# 2018_Dashboard.net
KiCad netlist of a schematic drawn in EAGLE
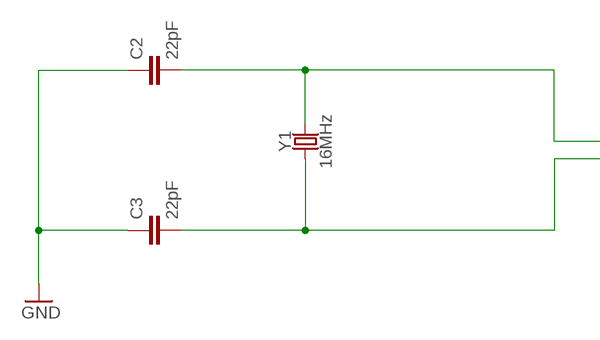
[diagram p0: schematic, sheet 1, part 1 of 2]
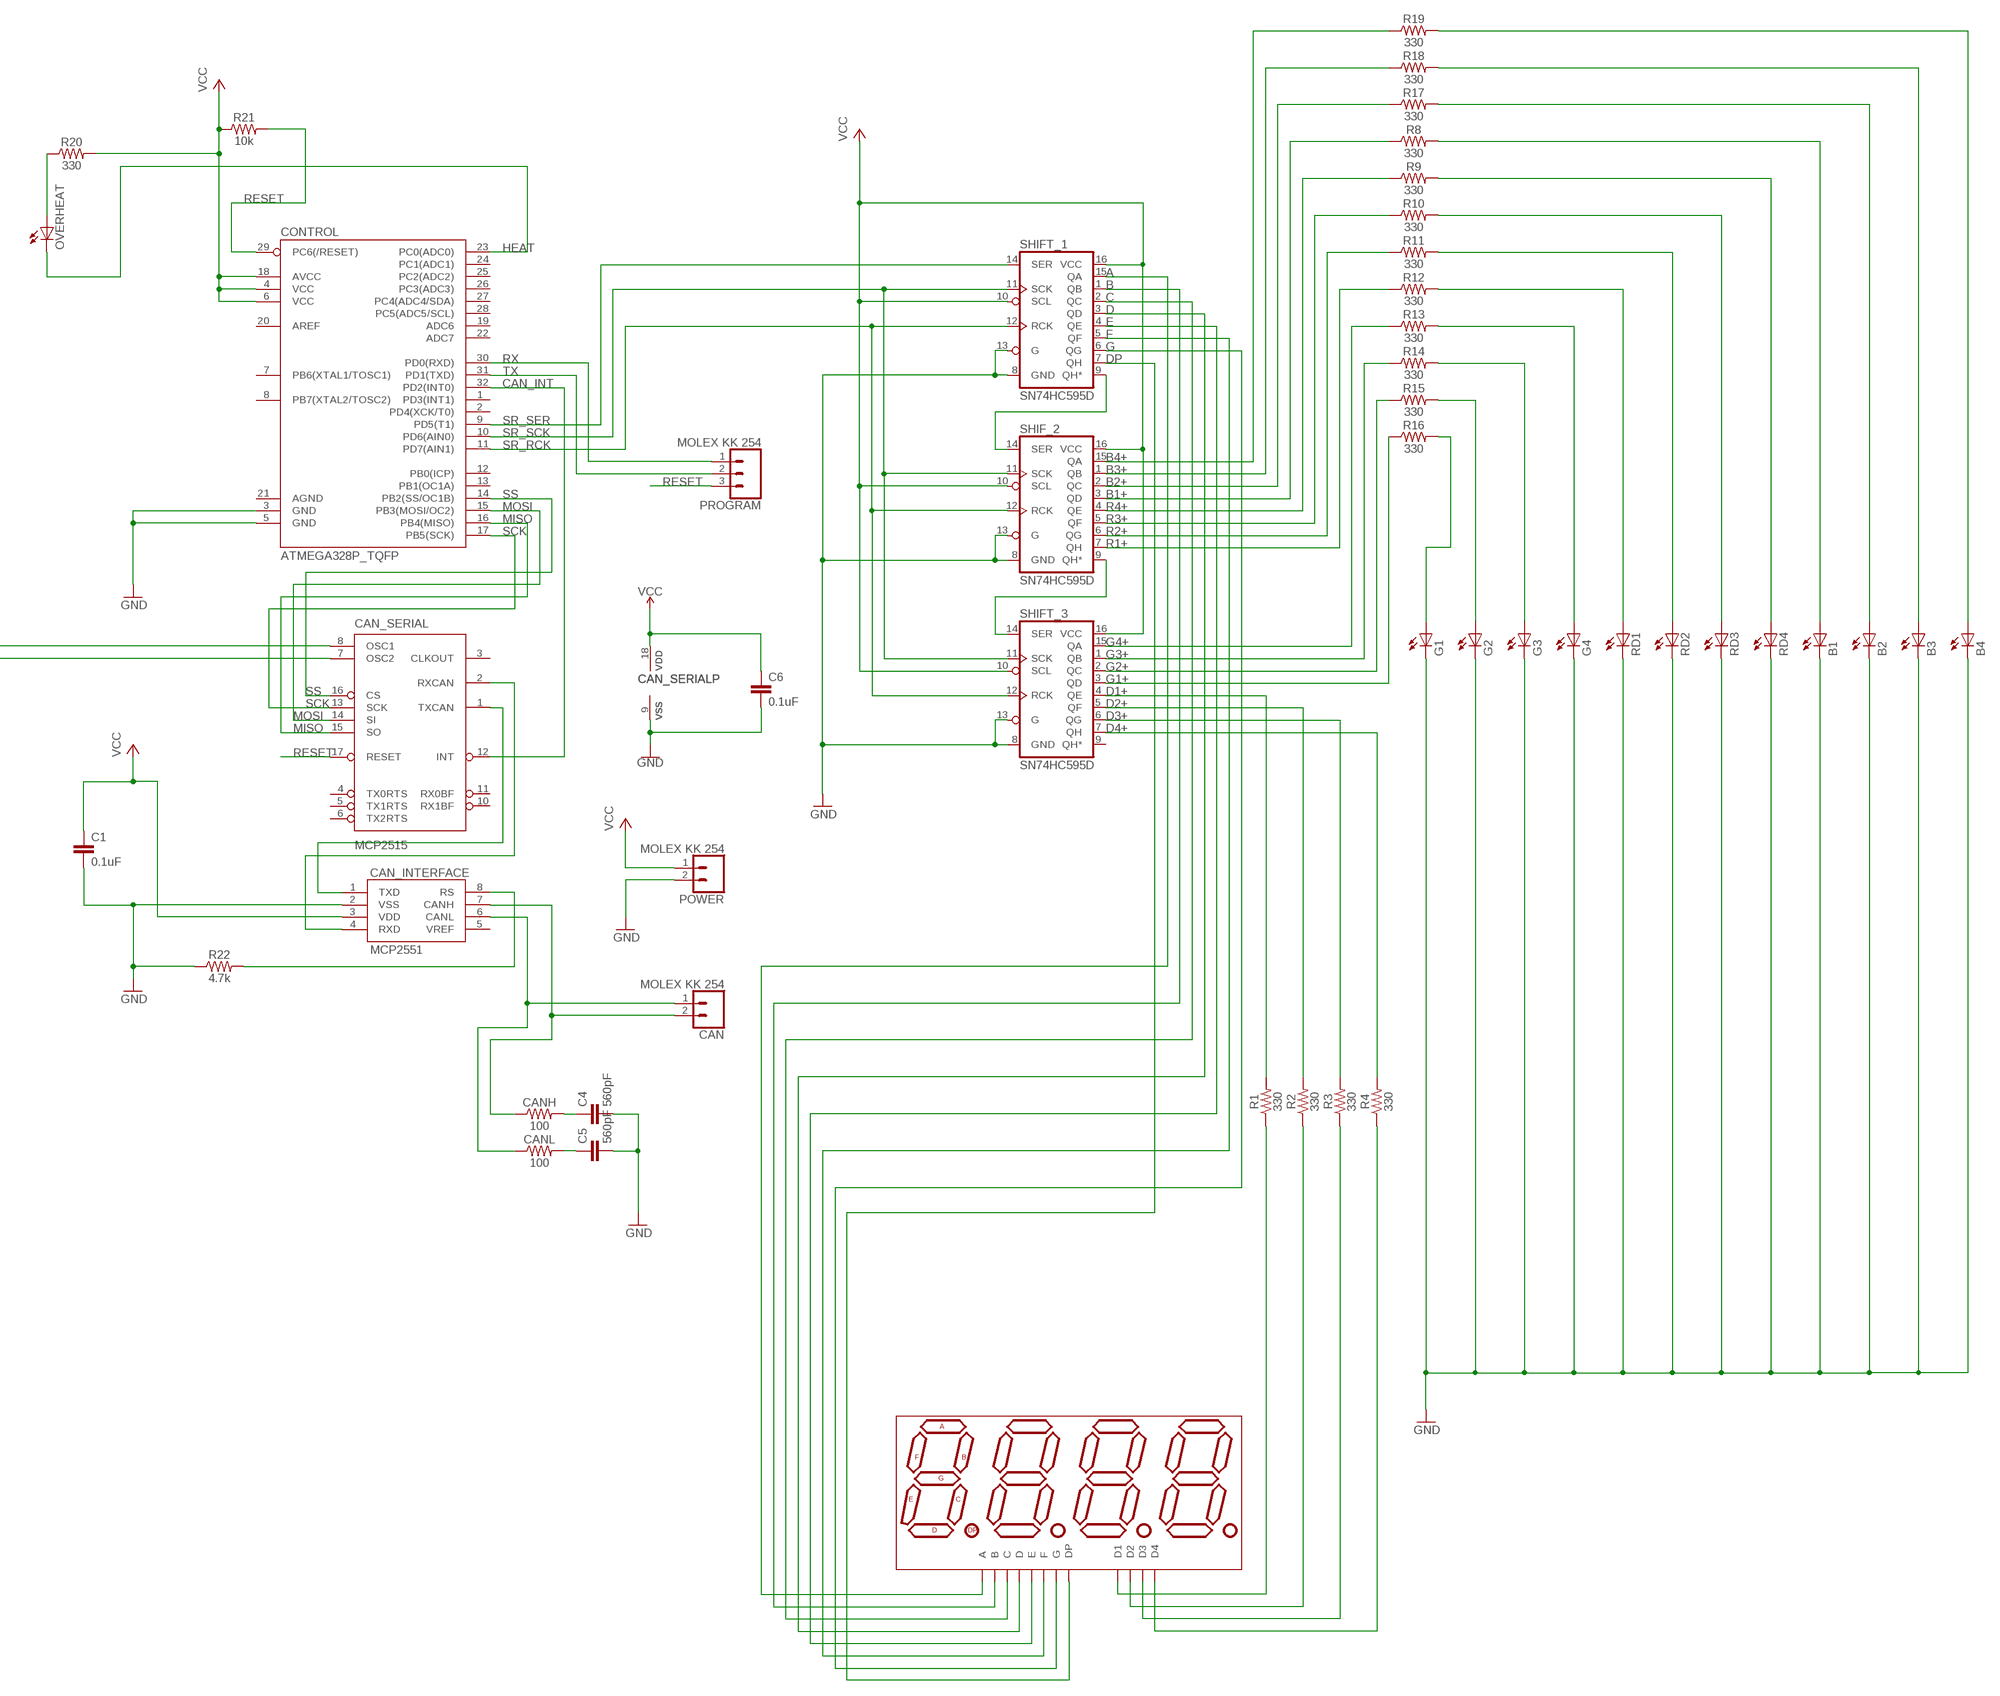
[diagram p1: schematic, sheet 1, part 2 of 2]

(export (version "E")
  (design (tool "Eeschema 10.0.6"))
  (components
    (comp (ref "B1")
      (value "TLLG4400")
      (footprint "eagle-import:LED3MM")
      (fields (field (name "MF") "VISHAY SEMICONDUCTOR"))
      (libsource (lib "eagle-import") (part "TLLG4400"))
    )
    (comp (ref "B2")
      (value "TLLG4400")
      (footprint "eagle-import:LED3MM")
      (fields (field (name "MF") "VISHAY SEMICONDUCTOR"))
      (libsource (lib "eagle-import") (part "TLLG4400"))
    )
    (comp (ref "B3")
      (value "TLLG4400")
      (footprint "eagle-import:LED3MM")
      (fields (field (name "MF") "VISHAY SEMICONDUCTOR"))
      (libsource (lib "eagle-import") (part "TLLG4400"))
    )
    (comp (ref "B4")
      (value "TLLG4400")
      (footprint "eagle-import:LED3MM")
      (fields (field (name "MF") "VISHAY SEMICONDUCTOR"))
      (libsource (lib "eagle-import") (part "TLLG4400"))
    )
    (comp (ref "C1")
      (value "0.1uF")
      (footprint "eagle-import:0603")
      (libsource (lib "eagle-import") (part "0.1UF-0603-25V-(+80/-20%)"))
    )
    (comp (ref "C2")
      (value "22pF")
      (footprint "eagle-import:0603")
      (libsource (lib "eagle-import") (part "22PF-0603-50V-5%"))
    )
    (comp (ref "C3")
      (value "22pF")
      (footprint "eagle-import:0603")
      (libsource (lib "eagle-import") (part "22PF-0603-50V-5%"))
    )
    (comp (ref "C4")
      (value "560pF")
      (footprint "eagle-import:0603")
      (libsource (lib "eagle-import") (part "560PF-0603-50V-5%"))
    )
    (comp (ref "C5")
      (value "560pF")
      (footprint "eagle-import:0603")
      (libsource (lib "eagle-import") (part "560PF-0603-50V-5%"))
    )
    (comp (ref "C6")
      (value "0.1uF")
      (footprint "eagle-import:0402")
      (libsource (lib "eagle-import") (part "0.1UF-0402-16V-10%"))
    )
    (comp (ref "CAN")
      (value "MOLEX KK 254")
      (footprint "eagle-import:1X02")
      (libsource (lib "eagle-import") (part "CONN_02"))
    )
    (comp (ref "CANH")
      (value "100")
      (footprint "eagle-import:0603")
      (libsource (lib "eagle-import") (part "100OHM-0603-1/4W-5%"))
    )
    (comp (ref "CANL")
      (value "100")
      (footprint "eagle-import:0603")
      (libsource (lib "eagle-import") (part "100OHM-0603-1/4W-5%"))
    )
    (comp (ref "CAN_INTERFACE")
      (value "MCP2551")
      (footprint "eagle-import:SO08")
      (libsource (lib "eagle-import") (part "MCP2551"))
    )
    (comp (ref "CAN_SERIAL")
      (value "MCP2515")
      (footprint "eagle-import:SO18W")
      (libsource (lib "eagle-import") (part "MCP2515(MCP2510)SO"))
    )
    (comp (ref "CONTROL")
      (value "ATMEGA328P_TQFP")
      (footprint "eagle-import:TQFP32-08")
      (libsource (lib "eagle-import") (part "ATMEGA328P_TQFP"))
    )
    (comp (ref "G1")
      (value "TLLG4400")
      (footprint "eagle-import:LED3MM")
      (fields (field (name "MF") "VISHAY SEMICONDUCTOR"))
      (libsource (lib "eagle-import") (part "TLLG4400"))
    )
    (comp (ref "G2")
      (value "TLLG4400")
      (footprint "eagle-import:LED3MM")
      (fields (field (name "MF") "VISHAY SEMICONDUCTOR"))
      (libsource (lib "eagle-import") (part "TLLG4400"))
    )
    (comp (ref "G3")
      (value "TLLG4400")
      (footprint "eagle-import:LED3MM")
      (fields (field (name "MF") "VISHAY SEMICONDUCTOR"))
      (libsource (lib "eagle-import") (part "TLLG4400"))
    )
    (comp (ref "G4")
      (value "TLLG4400")
      (footprint "eagle-import:LED3MM")
      (fields (field (name "MF") "VISHAY SEMICONDUCTOR"))
      (libsource (lib "eagle-import") (part "TLLG4400"))
    )
    (comp (ref "OVERHEAT")
      (value "TLLG4400")
      (footprint "eagle-import:LED3MM")
      (fields (field (name "MF") "VISHAY SEMICONDUCTOR"))
      (libsource (lib "eagle-import") (part "TLLG4400"))
    )
    (comp (ref "POWER")
      (value "MOLEX KK 254")
      (footprint "eagle-import:1X02")
      (libsource (lib "eagle-import") (part "CONN_02"))
    )
    (comp (ref "PROGRAM")
      (value "MOLEX KK 254")
      (footprint "eagle-import:1X03")
      (libsource (lib "eagle-import") (part "CONN_03"))
    )
    (comp (ref "R1")
      (value "330")
      (footprint "eagle-import:0603")
      (libsource (lib "eagle-import") (part "330OHM-0603-1/10W-1%"))
    )
    (comp (ref "R2")
      (value "330")
      (footprint "eagle-import:0603")
      (libsource (lib "eagle-import") (part "330OHM-0603-1/10W-1%"))
    )
    (comp (ref "R3")
      (value "330")
      (footprint "eagle-import:0603")
      (libsource (lib "eagle-import") (part "330OHM-0603-1/10W-1%"))
    )
    (comp (ref "R4")
      (value "330")
      (footprint "eagle-import:0603")
      (libsource (lib "eagle-import") (part "330OHM-0603-1/10W-1%"))
    )
    (comp (ref "R8")
      (value "330")
      (footprint "eagle-import:0603")
      (libsource (lib "eagle-import") (part "330OHM-0603-1/10W-1%"))
    )
    (comp (ref "R9")
      (value "330")
      (footprint "eagle-import:0603")
      (libsource (lib "eagle-import") (part "330OHM-0603-1/10W-1%"))
    )
    (comp (ref "R10")
      (value "330")
      (footprint "eagle-import:0603")
      (libsource (lib "eagle-import") (part "330OHM-0603-1/10W-1%"))
    )
    (comp (ref "R11")
      (value "330")
      (footprint "eagle-import:0603")
      (libsource (lib "eagle-import") (part "330OHM-0603-1/10W-1%"))
    )
    (comp (ref "R12")
      (value "330")
      (footprint "eagle-import:0603")
      (libsource (lib "eagle-import") (part "330OHM-0603-1/10W-1%"))
    )
    (comp (ref "R13")
      (value "330")
      (footprint "eagle-import:0603")
      (libsource (lib "eagle-import") (part "330OHM-0603-1/10W-1%"))
    )
    (comp (ref "R14")
      (value "330")
      (footprint "eagle-import:0603")
      (libsource (lib "eagle-import") (part "330OHM-0603-1/10W-1%"))
    )
    (comp (ref "R15")
      (value "330")
      (footprint "eagle-import:0603")
      (libsource (lib "eagle-import") (part "330OHM-0603-1/10W-1%"))
    )
    (comp (ref "R16")
      (value "330")
      (footprint "eagle-import:0603")
      (libsource (lib "eagle-import") (part "330OHM-0603-1/10W-1%"))
    )
    (comp (ref "R17")
      (value "330")
      (footprint "eagle-import:0603")
      (libsource (lib "eagle-import") (part "330OHM-0603-1/10W-1%"))
    )
    (comp (ref "R18")
      (value "330")
      (footprint "eagle-import:0603")
      (libsource (lib "eagle-import") (part "330OHM-0603-1/10W-1%"))
    )
    (comp (ref "R19")
      (value "330")
      (footprint "eagle-import:0603")
      (libsource (lib "eagle-import") (part "330OHM-0603-1/10W-1%"))
    )
    (comp (ref "R20")
      (value "330")
      (footprint "eagle-import:0603")
      (libsource (lib "eagle-import") (part "330OHM-0603-1/10W-1%"))
    )
    (comp (ref "R21")
      (value "10k")
      (footprint "eagle-import:0603")
      (libsource (lib "eagle-import") (part "10KOHM-0603-1/10W-1%"))
    )
    (comp (ref "R22")
      (value "4.7k")
      (footprint "eagle-import:0603")
      (libsource (lib "eagle-import") (part "4.7KOHM-0603-1/10W-1%"))
    )
    (comp (ref "RD1")
      (value "TLLG4400")
      (footprint "eagle-import:LED3MM")
      (fields (field (name "MF") "VISHAY SEMICONDUCTOR"))
      (libsource (lib "eagle-import") (part "TLLG4400"))
    )
    (comp (ref "RD2")
      (value "TLLG4400")
      (footprint "eagle-import:LED3MM")
      (fields (field (name "MF") "VISHAY SEMICONDUCTOR"))
      (libsource (lib "eagle-import") (part "TLLG4400"))
    )
    (comp (ref "RD3")
      (value "TLLG4400")
      (footprint "eagle-import:LED3MM")
      (fields (field (name "MF") "VISHAY SEMICONDUCTOR"))
      (libsource (lib "eagle-import") (part "TLLG4400"))
    )
    (comp (ref "RD4")
      (value "TLLG4400")
      (footprint "eagle-import:LED3MM")
      (fields (field (name "MF") "VISHAY SEMICONDUCTOR"))
      (libsource (lib "eagle-import") (part "TLLG4400"))
    )
    (comp (ref "SEVEN_SEGMENT")
      (value "ATA8041AB")
      (footprint "eagle-import:7-SEGMENT-4DIGIT-20MM")
      (libsource (lib "eagle-import") (part "7-SEGMENT-4DIGIT-20MM-BLUE"))
    )
    (comp (ref "SHIFT_1")
      (value "SN74HC595D")
      (footprint "eagle-import:SO16")
      (libsource (lib "eagle-import") (part "74595DHC"))
    )
    (comp (ref "SHIFT_3")
      (value "SN74HC595D")
      (footprint "eagle-import:SO16")
      (libsource (lib "eagle-import") (part "74595DHC"))
    )
    (comp (ref "SHIF_2")
      (value "SN74HC595D")
      (footprint "eagle-import:SO16")
      (libsource (lib "eagle-import") (part "74595DHC"))
    )
    (comp (ref "Y1")
      (value "16MHz")
      (footprint "eagle-import:HC49US")
      (libsource (lib "eagle-import") (part "CRYSTAL-16MHZPTH-HC49US"))
    )
  )
  (nets
    (net (code "1") (name "/A") (class "Default")
      (node (ref "SEVEN_SEGMENT") (pin "11") (pinfunction "A_11") (pintype "bidirectional"))
      (node (ref "SHIFT_1") (pin "15") (pinfunction "QA_15") (pintype "tri_state"))
    )
    (net (code "2") (name "/B") (class "Default")
      (node (ref "SEVEN_SEGMENT") (pin "7") (pinfunction "B_7") (pintype "bidirectional"))
      (node (ref "SHIFT_1") (pin "1") (pinfunction "QB_1") (pintype "tri_state"))
    )
    (net (code "3") (name "/B1+") (class "Default")
      (node (ref "R8") (pin "1") (pinfunction "1_1") (pintype "passive"))
      (node (ref "SHIF_2") (pin "3") (pinfunction "QD_3") (pintype "tri_state"))
    )
    (net (code "4") (name "/B2+") (class "Default")
      (node (ref "R17") (pin "1") (pinfunction "1_1") (pintype "passive"))
      (node (ref "SHIF_2") (pin "2") (pinfunction "QC_2") (pintype "tri_state"))
    )
    (net (code "5") (name "/B3+") (class "Default")
      (node (ref "R18") (pin "1") (pinfunction "1_1") (pintype "passive"))
      (node (ref "SHIF_2") (pin "1") (pinfunction "QB_1") (pintype "tri_state"))
    )
    (net (code "6") (name "/B4+") (class "Default")
      (node (ref "R19") (pin "1") (pinfunction "1_1") (pintype "passive"))
      (node (ref "SHIF_2") (pin "15") (pinfunction "QA_15") (pintype "tri_state"))
    )
    (net (code "7") (name "/C") (class "Default")
      (node (ref "SEVEN_SEGMENT") (pin "4") (pinfunction "C_4") (pintype "bidirectional"))
      (node (ref "SHIFT_1") (pin "2") (pinfunction "QC_2") (pintype "tri_state"))
    )
    (net (code "8") (name "/CAN_INT") (class "Default")
      (node (ref "CAN_SERIAL") (pin "12") (pinfunction "INT_12") (pintype "output"))
      (node (ref "CONTROL") (pin "32") (pinfunction "PD2(INT0)_32") (pintype "bidirectional"))
    )
    (net (code "9") (name "/D") (class "Default")
      (node (ref "SEVEN_SEGMENT") (pin "2") (pinfunction "D_2") (pintype "bidirectional"))
      (node (ref "SHIFT_1") (pin "3") (pinfunction "QD_3") (pintype "tri_state"))
    )
    (net (code "10") (name "/D1+") (class "Default")
      (node (ref "R1") (pin "2") (pinfunction "2_2") (pintype "passive"))
      (node (ref "SHIFT_3") (pin "4") (pinfunction "QE_4") (pintype "tri_state"))
    )
    (net (code "11") (name "/D2+") (class "Default")
      (node (ref "R2") (pin "2") (pinfunction "2_2") (pintype "passive"))
      (node (ref "SHIFT_3") (pin "5") (pinfunction "QF_5") (pintype "tri_state"))
    )
    (net (code "12") (name "/D3+") (class "Default")
      (node (ref "R3") (pin "2") (pinfunction "2_2") (pintype "passive"))
      (node (ref "SHIFT_3") (pin "6") (pinfunction "QG_6") (pintype "tri_state"))
    )
    (net (code "13") (name "/D4+") (class "Default")
      (node (ref "R4") (pin "2") (pinfunction "2_2") (pintype "passive"))
      (node (ref "SHIFT_3") (pin "7") (pinfunction "QH_7") (pintype "tri_state"))
    )
    (net (code "14") (name "/DP") (class "Default")
      (node (ref "SEVEN_SEGMENT") (pin "3") (pinfunction "DP_3") (pintype "bidirectional"))
      (node (ref "SHIFT_1") (pin "7") (pinfunction "QH_7") (pintype "tri_state"))
    )
    (net (code "15") (name "/E") (class "Default")
      (node (ref "SEVEN_SEGMENT") (pin "1") (pinfunction "E_1") (pintype "bidirectional"))
      (node (ref "SHIFT_1") (pin "4") (pinfunction "QE_4") (pintype "tri_state"))
    )
    (net (code "16") (name "/F") (class "Default")
      (node (ref "SEVEN_SEGMENT") (pin "10") (pinfunction "F_10") (pintype "bidirectional"))
      (node (ref "SHIFT_1") (pin "5") (pinfunction "QF_5") (pintype "tri_state"))
    )
    (net (code "17") (name "/G") (class "Default")
      (node (ref "SEVEN_SEGMENT") (pin "5") (pinfunction "G_5") (pintype "bidirectional"))
      (node (ref "SHIFT_1") (pin "6") (pinfunction "QG_6") (pintype "tri_state"))
    )
    (net (code "18") (name "/G1+") (class "Default")
      (node (ref "R16") (pin "1") (pinfunction "1_1") (pintype "passive"))
      (node (ref "SHIFT_3") (pin "3") (pinfunction "QD_3") (pintype "tri_state"))
    )
    (net (code "19") (name "/G2+") (class "Default")
      (node (ref "R15") (pin "1") (pinfunction "1_1") (pintype "passive"))
      (node (ref "SHIFT_3") (pin "2") (pinfunction "QC_2") (pintype "tri_state"))
    )
    (net (code "20") (name "/G3+") (class "Default")
      (node (ref "R14") (pin "1") (pinfunction "1_1") (pintype "passive"))
      (node (ref "SHIFT_3") (pin "1") (pinfunction "QB_1") (pintype "tri_state"))
    )
    (net (code "21") (name "/G4+") (class "Default")
      (node (ref "R13") (pin "1") (pinfunction "1_1") (pintype "passive"))
      (node (ref "SHIFT_3") (pin "15") (pinfunction "QA_15") (pintype "tri_state"))
    )
    (net (code "22") (name "/HEAT") (class "Default")
      (node (ref "CONTROL") (pin "23") (pinfunction "PC0(ADC0)_23") (pintype "bidirectional"))
      (node (ref "OVERHEAT") (pin "K") (pinfunction "C_K") (pintype "passive"))
    )
    (net (code "23") (name "/MISO") (class "Default")
      (node (ref "CAN_SERIAL") (pin "15") (pinfunction "SO_15") (pintype "output"))
      (node (ref "CONTROL") (pin "16") (pinfunction "PB4(MISO)_16") (pintype "bidirectional"))
    )
    (net (code "24") (name "/MOSI") (class "Default")
      (node (ref "CAN_SERIAL") (pin "14") (pinfunction "SI_14") (pintype "input"))
      (node (ref "CONTROL") (pin "15") (pinfunction "PB3(MOSI/OC2)_15") (pintype "bidirectional"))
    )
    (net (code "25") (name "/R1+") (class "Default")
      (node (ref "R12") (pin "1") (pinfunction "1_1") (pintype "passive"))
      (node (ref "SHIF_2") (pin "7") (pinfunction "QH_7") (pintype "tri_state"))
    )
    (net (code "26") (name "/R2+") (class "Default")
      (node (ref "R11") (pin "1") (pinfunction "1_1") (pintype "passive"))
      (node (ref "SHIF_2") (pin "6") (pinfunction "QG_6") (pintype "tri_state"))
    )
    (net (code "27") (name "/R3+") (class "Default")
      (node (ref "R10") (pin "1") (pinfunction "1_1") (pintype "passive"))
      (node (ref "SHIF_2") (pin "5") (pinfunction "QF_5") (pintype "tri_state"))
    )
    (net (code "28") (name "/R4+") (class "Default")
      (node (ref "R9") (pin "1") (pinfunction "1_1") (pintype "passive"))
      (node (ref "SHIF_2") (pin "4") (pinfunction "QE_4") (pintype "tri_state"))
    )
    (net (code "29") (name "/RESET") (class "Default")
      (node (ref "CAN_SERIAL") (pin "17") (pinfunction "RESET_17") (pintype "input"))
      (node (ref "CONTROL") (pin "29") (pinfunction "PC6(/RESET)_29") (pintype "bidirectional"))
      (node (ref "PROGRAM") (pin "3") (pinfunction "3_3") (pintype "passive"))
      (node (ref "R21") (pin "2") (pinfunction "2_2") (pintype "passive"))
    )
    (net (code "30") (name "/RX") (class "Default")
      (node (ref "CONTROL") (pin "30") (pinfunction "PD0(RXD)_30") (pintype "bidirectional"))
      (node (ref "PROGRAM") (pin "1") (pinfunction "1_1") (pintype "passive"))
    )
    (net (code "31") (name "/SCK") (class "Default")
      (node (ref "CAN_SERIAL") (pin "13") (pinfunction "SCK_13") (pintype "input"))
      (node (ref "CONTROL") (pin "17") (pinfunction "PB5(SCK)_17") (pintype "bidirectional"))
    )
    (net (code "32") (name "/SR_RCK") (class "Default")
      (node (ref "CONTROL") (pin "11") (pinfunction "PD7(AIN1)_11") (pintype "bidirectional"))
      (node (ref "SHIFT_1") (pin "12") (pinfunction "RCK_12") (pintype "input"))
      (node (ref "SHIFT_3") (pin "12") (pinfunction "RCK_12") (pintype "input"))
      (node (ref "SHIF_2") (pin "12") (pinfunction "RCK_12") (pintype "input"))
    )
    (net (code "33") (name "/SR_SCK") (class "Default")
      (node (ref "CONTROL") (pin "10") (pinfunction "PD6(AIN0)_10") (pintype "bidirectional"))
      (node (ref "SHIFT_1") (pin "11") (pinfunction "SCK_11") (pintype "input"))
      (node (ref "SHIFT_3") (pin "11") (pinfunction "SCK_11") (pintype "input"))
      (node (ref "SHIF_2") (pin "11") (pinfunction "SCK_11") (pintype "input"))
    )
    (net (code "34") (name "/SR_SER") (class "Default")
      (node (ref "CONTROL") (pin "9") (pinfunction "PD5(T1)_9") (pintype "bidirectional"))
      (node (ref "SHIFT_1") (pin "14") (pinfunction "SER_14") (pintype "input"))
    )
    (net (code "35") (name "/SS") (class "Default")
      (node (ref "CAN_SERIAL") (pin "16") (pinfunction "CS_16") (pintype "input"))
      (node (ref "CONTROL") (pin "14") (pinfunction "PB2(SS/OC1B)_14") (pintype "bidirectional"))
    )
    (net (code "36") (name "/TX") (class "Default")
      (node (ref "CONTROL") (pin "31") (pinfunction "PD1(TXD)_31") (pintype "bidirectional"))
      (node (ref "PROGRAM") (pin "2") (pinfunction "2_2") (pintype "passive"))
    )
    (net (code "37") (name "GND") (class "Default")
      (node (ref "B1") (pin "K") (pinfunction "C_K") (pintype "passive"))
      (node (ref "B2") (pin "K") (pinfunction "C_K") (pintype "passive"))
      (node (ref "B3") (pin "K") (pinfunction "C_K") (pintype "passive"))
      (node (ref "B4") (pin "K") (pinfunction "C_K") (pintype "passive"))
      (node (ref "C1") (pin "2") (pinfunction "2_2") (pintype "passive"))
      (node (ref "C2") (pin "1") (pinfunction "1_1") (pintype "passive"))
      (node (ref "C3") (pin "1") (pinfunction "1_1") (pintype "passive"))
      (node (ref "C4") (pin "2") (pinfunction "2_2") (pintype "passive"))
      (node (ref "C5") (pin "2") (pinfunction "2_2") (pintype "passive"))
      (node (ref "C6") (pin "2") (pinfunction "2_2") (pintype "passive"))
      (node (ref "CAN_INTERFACE") (pin "2") (pinfunction "VSS_2") (pintype "bidirectional"))
      (node (ref "CAN_SERIAL") (pin "9") (pinfunction "VSS_9") (pintype "power_in"))
      (node (ref "CONTROL") (pin "3") (pinfunction "GND_3") (pintype "bidirectional"))
      (node (ref "CONTROL") (pin "5") (pinfunction "GND_5") (pintype "bidirectional"))
      (node (ref "G1") (pin "K") (pinfunction "C_K") (pintype "passive"))
      (node (ref "G2") (pin "K") (pinfunction "C_K") (pintype "passive"))
      (node (ref "G3") (pin "K") (pinfunction "C_K") (pintype "passive"))
      (node (ref "G4") (pin "K") (pinfunction "C_K") (pintype "passive"))
      (node (ref "POWER") (pin "2") (pinfunction "2_2") (pintype "passive"))
      (node (ref "R22") (pin "1") (pinfunction "1_1") (pintype "passive"))
      (node (ref "RD1") (pin "K") (pinfunction "C_K") (pintype "passive"))
      (node (ref "RD2") (pin "K") (pinfunction "C_K") (pintype "passive"))
      (node (ref "RD3") (pin "K") (pinfunction "C_K") (pintype "passive"))
      (node (ref "RD4") (pin "K") (pinfunction "C_K") (pintype "passive"))
      (node (ref "SHIFT_1") (pin "13") (pinfunction "G_13") (pintype "input"))
      (node (ref "SHIFT_1") (pin "8") (pinfunction "GND_8") (pintype "power_in"))
      (node (ref "SHIFT_3") (pin "13") (pinfunction "G_13") (pintype "input"))
      (node (ref "SHIFT_3") (pin "8") (pinfunction "GND_8") (pintype "power_in"))
      (node (ref "SHIF_2") (pin "13") (pinfunction "G_13") (pintype "input"))
      (node (ref "SHIF_2") (pin "8") (pinfunction "GND_8") (pintype "power_in"))
    )
    (net (code "38") (name "Net-(B1-PadA)") (class "Default")
      (node (ref "B1") (pin "A") (pinfunction "A_A") (pintype "passive"))
      (node (ref "R8") (pin "2") (pinfunction "2_2") (pintype "passive"))
    )
    (net (code "39") (name "Net-(B2-PadA)") (class "Default")
      (node (ref "B2") (pin "A") (pinfunction "A_A") (pintype "passive"))
      (node (ref "R17") (pin "2") (pinfunction "2_2") (pintype "passive"))
    )
    (net (code "40") (name "Net-(B3-PadA)") (class "Default")
      (node (ref "B3") (pin "A") (pinfunction "A_A") (pintype "passive"))
      (node (ref "R18") (pin "2") (pinfunction "2_2") (pintype "passive"))
    )
    (net (code "41") (name "Net-(B4-PadA)") (class "Default")
      (node (ref "B4") (pin "A") (pinfunction "A_A") (pintype "passive"))
      (node (ref "R19") (pin "2") (pinfunction "2_2") (pintype "passive"))
    )
    (net (code "42") (name "Net-(C4-Pad1)") (class "Default")
      (node (ref "C4") (pin "1") (pinfunction "1_1") (pintype "passive"))
      (node (ref "CANH") (pin "2") (pinfunction "2_2") (pintype "passive"))
    )
    (net (code "43") (name "Net-(C5-Pad1)") (class "Default")
      (node (ref "C5") (pin "1") (pinfunction "1_1") (pintype "passive"))
      (node (ref "CANL") (pin "2") (pinfunction "2_2") (pintype "passive"))
    )
    (net (code "44") (name "Net-(CAN_INTERFACE-CANH)") (class "Default")
      (node (ref "CAN") (pin "2") (pinfunction "2_2") (pintype "passive"))
      (node (ref "CANH") (pin "1") (pinfunction "1_1") (pintype "passive"))
      (node (ref "CAN_INTERFACE") (pin "7") (pinfunction "CANH_7") (pintype "bidirectional"))
    )
    (net (code "45") (name "Net-(CAN_INTERFACE-CANL)") (class "Default")
      (node (ref "CAN") (pin "1") (pinfunction "1_1") (pintype "passive"))
      (node (ref "CANL") (pin "1") (pinfunction "1_1") (pintype "passive"))
      (node (ref "CAN_INTERFACE") (pin "6") (pinfunction "CANL_6") (pintype "bidirectional"))
    )
    (net (code "46") (name "Net-(CAN_INTERFACE-RS)") (class "Default")
      (node (ref "CAN_INTERFACE") (pin "8") (pinfunction "RS_8") (pintype "bidirectional"))
      (node (ref "R22") (pin "2") (pinfunction "2_2") (pintype "passive"))
    )
    (net (code "47") (name "Net-(CAN_INTERFACE-RXD)") (class "Default")
      (node (ref "CAN_INTERFACE") (pin "4") (pinfunction "RXD_4") (pintype "bidirectional"))
      (node (ref "CAN_SERIAL") (pin "2") (pinfunction "RXCAN_2") (pintype "input"))
    )
    (net (code "48") (name "Net-(CAN_INTERFACE-TXD)") (class "Default")
      (node (ref "CAN_INTERFACE") (pin "1") (pinfunction "TXD_1") (pintype "bidirectional"))
      (node (ref "CAN_SERIAL") (pin "1") (pinfunction "TXCAN_1") (pintype "output"))
    )
    (net (code "49") (name "Net-(CAN_SERIALA-OSC1)") (class "Default")
      (node (ref "C2") (pin "2") (pinfunction "2_2") (pintype "passive"))
      (node (ref "CAN_SERIAL") (pin "8") (pinfunction "OSC1_8") (pintype "input"))
      (node (ref "Y1") (pin "2") (pinfunction "2_2") (pintype "passive"))
    )
    (net (code "50") (name "Net-(CAN_SERIALA-OSC2)") (class "Default")
      (node (ref "C3") (pin "2") (pinfunction "2_2") (pintype "passive"))
      (node (ref "CAN_SERIAL") (pin "7") (pinfunction "OSC2_7") (pintype "output"))
      (node (ref "Y1") (pin "1") (pinfunction "1_1") (pintype "passive"))
    )
    (net (code "51") (name "Net-(G1-PadA)") (class "Default")
      (node (ref "G1") (pin "A") (pinfunction "A_A") (pintype "passive"))
      (node (ref "R16") (pin "2") (pinfunction "2_2") (pintype "passive"))
    )
    (net (code "52") (name "Net-(G2-PadA)") (class "Default")
      (node (ref "G2") (pin "A") (pinfunction "A_A") (pintype "passive"))
      (node (ref "R15") (pin "2") (pinfunction "2_2") (pintype "passive"))
    )
    (net (code "53") (name "Net-(G3-PadA)") (class "Default")
      (node (ref "G3") (pin "A") (pinfunction "A_A") (pintype "passive"))
      (node (ref "R14") (pin "2") (pinfunction "2_2") (pintype "passive"))
    )
    (net (code "54") (name "Net-(G4-PadA)") (class "Default")
      (node (ref "G4") (pin "A") (pinfunction "A_A") (pintype "passive"))
      (node (ref "R13") (pin "2") (pinfunction "2_2") (pintype "passive"))
    )
    (net (code "55") (name "Net-(OVERHEAT-PadA)") (class "Default")
      (node (ref "OVERHEAT") (pin "A") (pinfunction "A_A") (pintype "passive"))
      (node (ref "R20") (pin "1") (pinfunction "1_1") (pintype "passive"))
    )
    (net (code "56") (name "Net-(R9-Pad2)") (class "Default")
      (node (ref "R9") (pin "2") (pinfunction "2_2") (pintype "passive"))
      (node (ref "RD4") (pin "A") (pinfunction "A_A") (pintype "passive"))
    )
    (net (code "57") (name "Net-(R10-Pad2)") (class "Default")
      (node (ref "R10") (pin "2") (pinfunction "2_2") (pintype "passive"))
      (node (ref "RD3") (pin "A") (pinfunction "A_A") (pintype "passive"))
    )
    (net (code "58") (name "Net-(R11-Pad2)") (class "Default")
      (node (ref "R11") (pin "2") (pinfunction "2_2") (pintype "passive"))
      (node (ref "RD2") (pin "A") (pinfunction "A_A") (pintype "passive"))
    )
    (net (code "59") (name "Net-(R12-Pad2)") (class "Default")
      (node (ref "R12") (pin "2") (pinfunction "2_2") (pintype "passive"))
      (node (ref "RD1") (pin "A") (pinfunction "A_A") (pintype "passive"))
    )
    (net (code "60") (name "Net-(SEVEN_SEGMENT-D1)") (class "Default")
      (node (ref "R1") (pin "1") (pinfunction "1_1") (pintype "passive"))
      (node (ref "SEVEN_SEGMENT") (pin "12") (pinfunction "D1_12") (pintype "bidirectional"))
    )
    (net (code "61") (name "Net-(SEVEN_SEGMENT-D2)") (class "Default")
      (node (ref "R2") (pin "1") (pinfunction "1_1") (pintype "passive"))
      (node (ref "SEVEN_SEGMENT") (pin "9") (pinfunction "D2_9") (pintype "bidirectional"))
    )
    (net (code "62") (name "Net-(SEVEN_SEGMENT-D3)") (class "Default")
      (node (ref "R3") (pin "1") (pinfunction "1_1") (pintype "passive"))
      (node (ref "SEVEN_SEGMENT") (pin "8") (pinfunction "D3_8") (pintype "bidirectional"))
    )
    (net (code "63") (name "Net-(SEVEN_SEGMENT-D4)") (class "Default")
      (node (ref "R4") (pin "1") (pinfunction "1_1") (pintype "passive"))
      (node (ref "SEVEN_SEGMENT") (pin "6") (pinfunction "D4_6") (pintype "bidirectional"))
    )
    (net (code "64") (name "Net-(SHIFT_1-QH*)") (class "Default")
      (node (ref "SHIFT_1") (pin "9") (pinfunction "QH*_9") (pintype "tri_state"))
      (node (ref "SHIF_2") (pin "14") (pinfunction "SER_14") (pintype "input"))
    )
    (net (code "65") (name "Net-(SHIFT_3-SER)") (class "Default")
      (node (ref "SHIFT_3") (pin "14") (pinfunction "SER_14") (pintype "input"))
      (node (ref "SHIF_2") (pin "9") (pinfunction "QH*_9") (pintype "tri_state"))
    )
    (net (code "66") (name "VCC") (class "Default")
      (node (ref "C1") (pin "1") (pinfunction "1_1") (pintype "passive"))
      (node (ref "C6") (pin "1") (pinfunction "1_1") (pintype "passive"))
      (node (ref "CAN_INTERFACE") (pin "3") (pinfunction "VDD_3") (pintype "bidirectional"))
      (node (ref "CAN_SERIAL") (pin "18") (pinfunction "VDD_18") (pintype "power_in"))
      (node (ref "CONTROL") (pin "18") (pinfunction "AVCC_18") (pintype "bidirectional"))
      (node (ref "CONTROL") (pin "4") (pinfunction "VCC_4") (pintype "bidirectional"))
      (node (ref "CONTROL") (pin "6") (pinfunction "VCC_6") (pintype "bidirectional"))
      (node (ref "POWER") (pin "1") (pinfunction "1_1") (pintype "passive"))
      (node (ref "R20") (pin "2") (pinfunction "2_2") (pintype "passive"))
      (node (ref "R21") (pin "1") (pinfunction "1_1") (pintype "passive"))
      (node (ref "SHIFT_1") (pin "10") (pinfunction "SCL_10") (pintype "input"))
      (node (ref "SHIFT_1") (pin "16") (pinfunction "VCC_16") (pintype "power_in"))
      (node (ref "SHIFT_3") (pin "10") (pinfunction "SCL_10") (pintype "input"))
      (node (ref "SHIFT_3") (pin "16") (pinfunction "VCC_16") (pintype "power_in"))
      (node (ref "SHIF_2") (pin "10") (pinfunction "SCL_10") (pintype "input"))
      (node (ref "SHIF_2") (pin "16") (pinfunction "VCC_16") (pintype "power_in"))
    )
    (net (code "67") (name "unconnected-(CAN_INTERFACE-VREF-Pad5)") (class "Default")
      (node (ref "CAN_INTERFACE") (pin "5") (pinfunction "VREF_5") (pintype "bidirectional"))
    )
    (net (code "68") (name "unconnected-(CAN_SERIALA-CLKOUT-Pad3)") (class "Default")
      (node (ref "CAN_SERIAL") (pin "3") (pinfunction "CLKOUT_3") (pintype "output"))
    )
    (net (code "69") (name "unconnected-(CAN_SERIALA-RX0BF-Pad11)") (class "Default")
      (node (ref "CAN_SERIAL") (pin "11") (pinfunction "RX0BF_11") (pintype "output"))
    )
    (net (code "70") (name "unconnected-(CAN_SERIALA-RX1BF-Pad10)") (class "Default")
      (node (ref "CAN_SERIAL") (pin "10") (pinfunction "RX1BF_10") (pintype "output"))
    )
    (net (code "71") (name "unconnected-(CAN_SERIALA-TX0RTS-Pad4)") (class "Default")
      (node (ref "CAN_SERIAL") (pin "4") (pinfunction "TX0RTS_4") (pintype "input"))
    )
    (net (code "72") (name "unconnected-(CAN_SERIALA-TX1RTS-Pad5)") (class "Default")
      (node (ref "CAN_SERIAL") (pin "5") (pinfunction "TX1RTS_5") (pintype "input"))
    )
    (net (code "73") (name "unconnected-(CAN_SERIALA-TX2RTS-Pad6)") (class "Default")
      (node (ref "CAN_SERIAL") (pin "6") (pinfunction "TX2RTS_6") (pintype "input"))
    )
    (net (code "74") (name "unconnected-(CONTROL-ADC6-Pad19)") (class "Default")
      (node (ref "CONTROL") (pin "19") (pinfunction "ADC6_19") (pintype "bidirectional"))
    )
    (net (code "75") (name "unconnected-(CONTROL-ADC7-Pad22)") (class "Default")
      (node (ref "CONTROL") (pin "22") (pinfunction "ADC7_22") (pintype "bidirectional"))
    )
    (net (code "76") (name "unconnected-(CONTROL-AGND-Pad21)") (class "Default")
      (node (ref "CONTROL") (pin "21") (pinfunction "AGND_21") (pintype "bidirectional"))
    )
    (net (code "77") (name "unconnected-(CONTROL-AREF-Pad20)") (class "Default")
      (node (ref "CONTROL") (pin "20") (pinfunction "AREF_20") (pintype "bidirectional"))
    )
    (net (code "78") (name "unconnected-(CONTROL-PB0(ICP)-Pad12)") (class "Default")
      (node (ref "CONTROL") (pin "12") (pinfunction "PB0(ICP)_12") (pintype "bidirectional"))
    )
    (net (code "79") (name "unconnected-(CONTROL-PB1(OC1A)-Pad13)") (class "Default")
      (node (ref "CONTROL") (pin "13") (pinfunction "PB1(OC1A)_13") (pintype "bidirectional"))
    )
    (net (code "80") (name "unconnected-(CONTROL-PB6(XTAL1{slash}TOSC1)-Pad7)") (class "Default")
      (node (ref "CONTROL") (pin "7") (pinfunction "PB6(XTAL1/TOSC1)_7") (pintype "bidirectional"))
    )
    (net (code "81") (name "unconnected-(CONTROL-PB7(XTAL2{slash}TOSC2)-Pad8)") (class "Default")
      (node (ref "CONTROL") (pin "8") (pinfunction "PB7(XTAL2/TOSC2)_8") (pintype "bidirectional"))
    )
    (net (code "82") (name "unconnected-(CONTROL-PC1(ADC1)-Pad24)") (class "Default")
      (node (ref "CONTROL") (pin "24") (pinfunction "PC1(ADC1)_24") (pintype "bidirectional"))
    )
    (net (code "83") (name "unconnected-(CONTROL-PC2(ADC2)-Pad25)") (class "Default")
      (node (ref "CONTROL") (pin "25") (pinfunction "PC2(ADC2)_25") (pintype "bidirectional"))
    )
    (net (code "84") (name "unconnected-(CONTROL-PC3(ADC3)-Pad26)") (class "Default")
      (node (ref "CONTROL") (pin "26") (pinfunction "PC3(ADC3)_26") (pintype "bidirectional"))
    )
    (net (code "85") (name "unconnected-(CONTROL-PC4(ADC4{slash}SDA)-Pad27)") (class "Default")
      (node (ref "CONTROL") (pin "27") (pinfunction "PC4(ADC4/SDA)_27") (pintype "bidirectional"))
    )
    (net (code "86") (name "unconnected-(CONTROL-PC5(ADC5{slash}SCL)-Pad28)") (class "Default")
      (node (ref "CONTROL") (pin "28") (pinfunction "PC5(ADC5/SCL)_28") (pintype "bidirectional"))
    )
    (net (code "87") (name "unconnected-(CONTROL-PD3(INT1)-Pad1)") (class "Default")
      (node (ref "CONTROL") (pin "1") (pinfunction "PD3(INT1)_1") (pintype "bidirectional"))
    )
    (net (code "88") (name "unconnected-(CONTROL-PD4(XCK{slash}T0)-Pad2)") (class "Default")
      (node (ref "CONTROL") (pin "2") (pinfunction "PD4(XCK/T0)_2") (pintype "bidirectional"))
    )
    (net (code "89") (name "unconnected-(SHIFT_3-QH*-Pad9)") (class "Default")
      (node (ref "SHIFT_3") (pin "9") (pinfunction "QH*_9") (pintype "tri_state"))
    )
  )
)
